# TIVA_1.net
KiCad netlist of a schematic drawn in Altium Designer
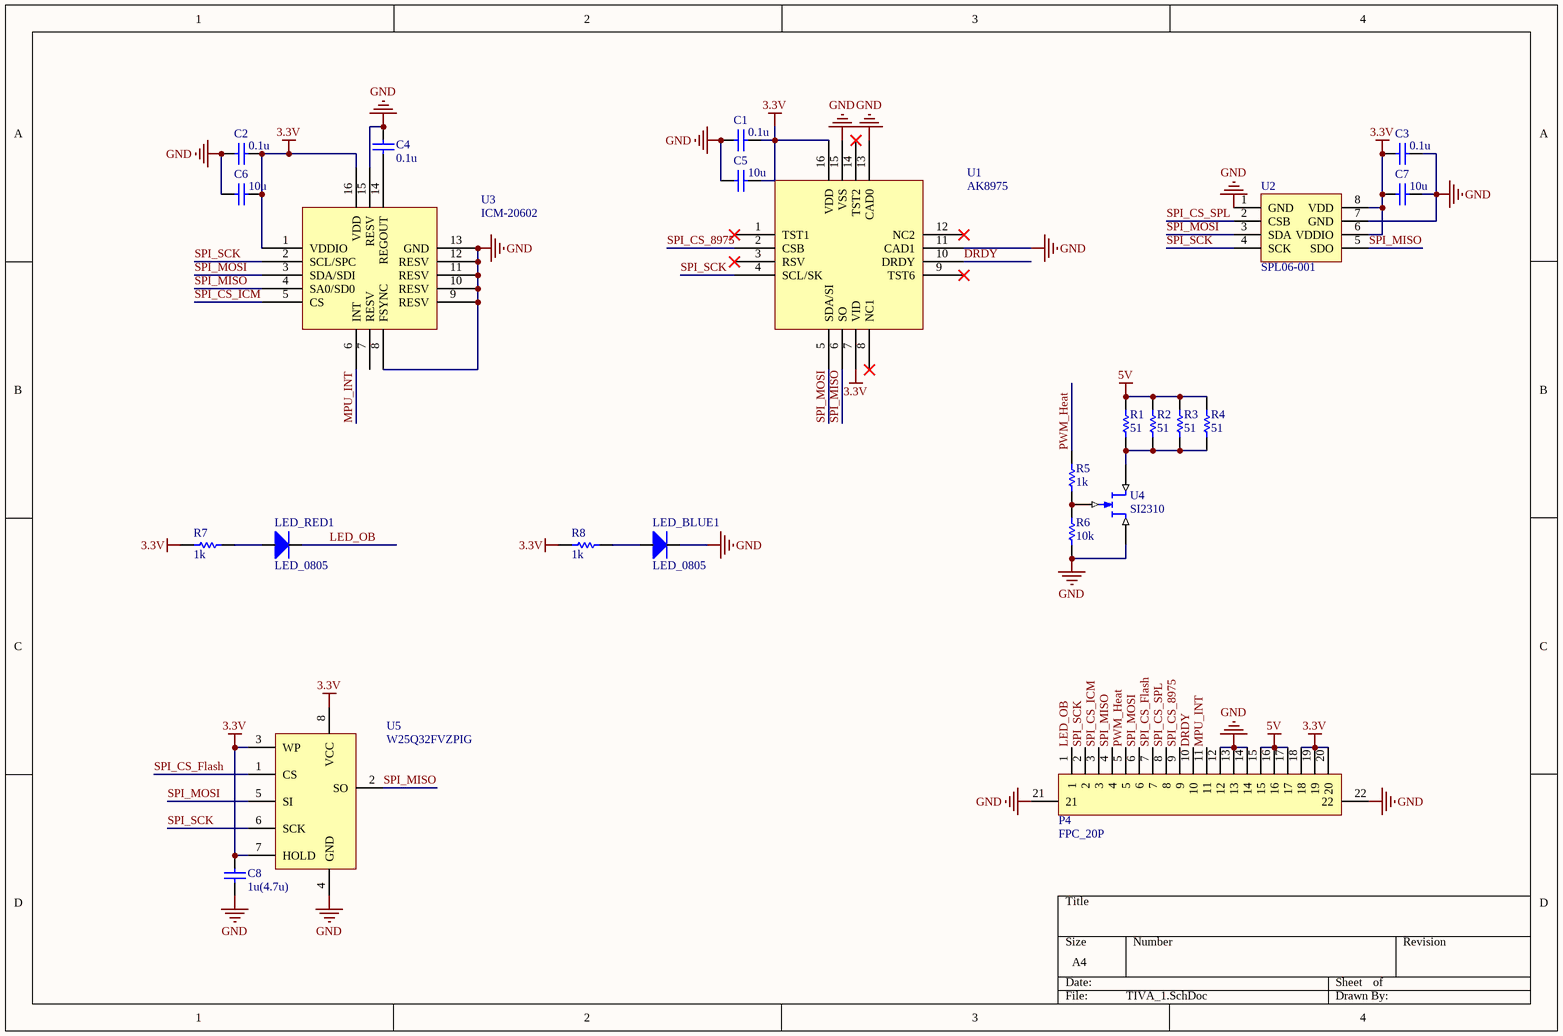
[diagram p0: TIVA_1.SchDoc]

(export (version "E")
  (design (tool "Eeschema 10.0.6"))
  (components
    (comp (ref "C1") (value "0.1u") (footprint "C_0805") (libsource (lib "TIVALib") (part "C_0805")))
    (comp (ref "C2") (value "0.1u") (footprint "C_0805") (libsource (lib "TIVALib") (part "C_0805")))
    (comp (ref "C3") (value "0.1u") (footprint "C_0805") (libsource (lib "TIVALib") (part "C_0805")))
    (comp (ref "C4") (value "0.1u") (footprint "C_0805") (libsource (lib "TIVALib") (part "C_0805")))
    (comp (ref "C5") (value "10u") (footprint "C_0805") (libsource (lib "TIVALib") (part "C_0805")))
    (comp (ref "C6") (value "10u") (footprint "C_0805") (libsource (lib "TIVALib") (part "C_0805")))
    (comp (ref "C7") (value "10u") (footprint "C_0805") (libsource (lib "TIVALib") (part "C_0805")))
    (comp (ref "C8") (value "1u(4.7u)") (footprint "C_0805") (libsource (lib "TIVALib") (part "C_0805")))
    (comp (ref "LED_BLUE1")
      (value "LED_0805")
      (footprint "LED0805")
      (libsource (lib "TIVALib") (part "LED_0805"))
    )
    (comp (ref "LED_RED1")
      (value "LED_0805")
      (footprint "LED0805")
      (libsource (lib "TIVALib") (part "LED_0805"))
    )
    (comp (ref "P4") (value "FPC_20P") (footprint "FPC1.0_20P") (libsource (lib "TIVALib") (part "FPC_20P")))
    (comp (ref "R1") (value "51") (footprint "R_0805") (libsource (lib "TIVALib") (part "R_0805")))
    (comp (ref "R2") (value "51") (footprint "R_0805") (libsource (lib "TIVALib") (part "R_0805")))
    (comp (ref "R3") (value "51") (footprint "R_0805") (libsource (lib "TIVALib") (part "R_0805")))
    (comp (ref "R4") (value "51") (footprint "R_0805") (libsource (lib "TIVALib") (part "R_0805")))
    (comp (ref "R5") (value "1k") (footprint "R_0805") (libsource (lib "TIVALib") (part "R_0805")))
    (comp (ref "R6") (value "10k") (footprint "R_0805") (libsource (lib "TIVALib") (part "R_0805")))
    (comp (ref "R7") (value "1k") (footprint "R_0805") (libsource (lib "TIVALib") (part "R_0805")))
    (comp (ref "R8") (value "1k") (footprint "R_0805") (libsource (lib "TIVALib") (part "R_0805")))
    (comp (ref "U1") (value "AK8975") (footprint "QFN16(4*4)") (libsource (lib "TIVALib") (part "AK8975")))
    (comp (ref "U2")
      (value "SPL06-001")
      (footprint "QFN8(2*4F)")
      (libsource (lib "TIVALib") (part "SPL06-001"))
    )
    (comp (ref "U3")
      (value "ICM-20602")
      (footprint "QFN16(3+5)")
      (libsource (lib "TIVALib") (part "ICM-20602"))
    )
    (comp (ref "U4") (value "SI2310") (footprint "SOT_23") (libsource (lib "TIVALib") (part "SI2310_2")))
    (comp (ref "U5")
      (value "W25Q32FVZPIG")
      (footprint "WSON(6*5mm)")
      (libsource (lib "TIVALib") (part "W25Q32FVZPIG"))
    )
  )
  (nets
    (net (code "1") (name "/DRDY") (class "Default")
      (node (ref "P4") (pin "10") (pinfunction "10_10") (pintype "passive"))
      (node (ref "U1") (pin "10") (pinfunction "DRDY_10") (pintype "passive"))
    )
    (net (code "2") (name "/LED_OB") (class "Default")
      (node (ref "LED_RED1") (pin "2") (pintype "passive"))
      (node (ref "P4") (pin "1") (pinfunction "1_1") (pintype "passive"))
    )
    (net (code "3") (name "/MPU_INT") (class "Default")
      (node (ref "P4") (pin "11") (pinfunction "11_11") (pintype "passive"))
      (node (ref "U3") (pin "6") (pinfunction "INT_6") (pintype "passive"))
    )
    (net (code "4") (name "/PWM_Heat") (class "Default")
      (node (ref "P4") (pin "5") (pinfunction "5_5") (pintype "passive"))
      (node (ref "R5") (pin "2") (pinfunction "2_2") (pintype "passive"))
    )
    (net (code "5") (name "/SPI_CS_8975") (class "Default")
      (node (ref "P4") (pin "9") (pinfunction "9_9") (pintype "passive"))
      (node (ref "U1") (pin "2") (pinfunction "CSB_2") (pintype "passive"))
    )
    (net (code "6") (name "/SPI_CS_Flash") (class "Default")
      (node (ref "P4") (pin "7") (pinfunction "7_7") (pintype "passive"))
      (node (ref "U5") (pin "1") (pinfunction "CS_1") (pintype "passive"))
    )
    (net (code "7") (name "/SPI_CS_ICM") (class "Default")
      (node (ref "P4") (pin "3") (pinfunction "3_3") (pintype "passive"))
      (node (ref "U3") (pin "5") (pinfunction "CS_5") (pintype "passive"))
    )
    (net (code "8") (name "/SPI_CS_SPL") (class "Default")
      (node (ref "P4") (pin "8") (pinfunction "8_8") (pintype "passive"))
      (node (ref "U2") (pin "2") (pinfunction "CSB_2") (pintype "passive"))
    )
    (net (code "9") (name "/SPI_MISO") (class "Default")
      (node (ref "P4") (pin "4") (pinfunction "4_4") (pintype "passive"))
      (node (ref "U1") (pin "6") (pinfunction "SO_6") (pintype "passive"))
      (node (ref "U2") (pin "5") (pinfunction "SDO_5") (pintype "passive"))
      (node (ref "U3") (pin "4") (pinfunction "SA0/SD0_4") (pintype "passive"))
      (node (ref "U5") (pin "2") (pinfunction "SO_2") (pintype "passive"))
    )
    (net (code "10") (name "/SPI_MOSI") (class "Default")
      (node (ref "P4") (pin "6") (pinfunction "6_6") (pintype "passive"))
      (node (ref "U1") (pin "5") (pinfunction "SDA/SI_5") (pintype "passive"))
      (node (ref "U2") (pin "3") (pinfunction "SDA_3") (pintype "passive"))
      (node (ref "U3") (pin "3") (pinfunction "SDA/SDI_3") (pintype "passive"))
      (node (ref "U5") (pin "5") (pinfunction "SI_5") (pintype "passive"))
    )
    (net (code "11") (name "/SPI_SCK") (class "Default")
      (node (ref "P4") (pin "2") (pinfunction "2_2") (pintype "passive"))
      (node (ref "U1") (pin "4") (pinfunction "SCL/SK_4") (pintype "passive"))
      (node (ref "U2") (pin "4") (pinfunction "SCK_4") (pintype "passive"))
      (node (ref "U3") (pin "2") (pinfunction "SCL/SPC_2") (pintype "passive"))
      (node (ref "U5") (pin "6") (pinfunction "SCK_6") (pintype "passive"))
    )
    (net (code "12") (name "3.3V") (class "Default")
      (node (ref "C1") (pin "1") (pinfunction "1_1") (pintype "passive"))
      (node (ref "C2") (pin "1") (pinfunction "1_1") (pintype "passive"))
      (node (ref "C3") (pin "2") (pinfunction "2_2") (pintype "passive"))
      (node (ref "C5") (pin "1") (pinfunction "1_1") (pintype "passive"))
      (node (ref "C6") (pin "1") (pinfunction "1_1") (pintype "passive"))
      (node (ref "C7") (pin "2") (pinfunction "2_2") (pintype "passive"))
      (node (ref "C8") (pin "1") (pinfunction "1_1") (pintype "passive"))
      (node (ref "P4") (pin "18") (pinfunction "18_18") (pintype "passive"))
      (node (ref "P4") (pin "19") (pinfunction "19_19") (pintype "passive"))
      (node (ref "P4") (pin "20") (pinfunction "20_20") (pintype "passive"))
      (node (ref "R7") (pin "1") (pinfunction "1_1") (pintype "passive"))
      (node (ref "R8") (pin "1") (pinfunction "1_1") (pintype "passive"))
      (node (ref "U1") (pin "16") (pinfunction "VDD_16") (pintype "passive"))
      (node (ref "U1") (pin "7") (pinfunction "VID_7") (pintype "passive"))
      (node (ref "U2") (pin "6") (pinfunction "VDDIO_6") (pintype "passive"))
      (node (ref "U2") (pin "8") (pinfunction "VDD_8") (pintype "passive"))
      (node (ref "U3") (pin "1") (pinfunction "VDDIO_1") (pintype "passive"))
      (node (ref "U3") (pin "16") (pinfunction "VDD_16") (pintype "passive"))
      (node (ref "U5") (pin "3") (pinfunction "WP_3") (pintype "passive"))
      (node (ref "U5") (pin "7") (pinfunction "HOLD_7") (pintype "passive"))
      (node (ref "U5") (pin "8") (pinfunction "VCC_8") (pintype "passive"))
    )
    (net (code "13") (name "5V") (class "Default")
      (node (ref "P4") (pin "15") (pinfunction "15_15") (pintype "passive"))
      (node (ref "P4") (pin "16") (pinfunction "16_16") (pintype "passive"))
      (node (ref "P4") (pin "17") (pinfunction "17_17") (pintype "passive"))
      (node (ref "R1") (pin "2") (pinfunction "2_2") (pintype "passive"))
      (node (ref "R2") (pin "2") (pinfunction "2_2") (pintype "passive"))
      (node (ref "R3") (pin "2") (pinfunction "2_2") (pintype "passive"))
      (node (ref "R4") (pin "2") (pinfunction "2_2") (pintype "passive"))
    )
    (net (code "14") (name "GND") (class "Default")
      (node (ref "C1") (pin "2") (pinfunction "2_2") (pintype "passive"))
      (node (ref "C2") (pin "2") (pinfunction "2_2") (pintype "passive"))
      (node (ref "C3") (pin "1") (pinfunction "1_1") (pintype "passive"))
      (node (ref "C4") (pin "2") (pinfunction "2_2") (pintype "passive"))
      (node (ref "C5") (pin "2") (pinfunction "2_2") (pintype "passive"))
      (node (ref "C6") (pin "2") (pinfunction "2_2") (pintype "passive"))
      (node (ref "C7") (pin "1") (pinfunction "1_1") (pintype "passive"))
      (node (ref "C8") (pin "2") (pinfunction "2_2") (pintype "passive"))
      (node (ref "LED_BLUE1") (pin "2") (pintype "passive"))
      (node (ref "P4") (pin "12") (pinfunction "12_12") (pintype "passive"))
      (node (ref "P4") (pin "13") (pinfunction "13_13") (pintype "passive"))
      (node (ref "P4") (pin "14") (pinfunction "14_14") (pintype "passive"))
      (node (ref "P4") (pin "21") (pinfunction "21_21") (pintype "passive"))
      (node (ref "P4") (pin "22") (pinfunction "22_22") (pintype "passive"))
      (node (ref "R6") (pin "1") (pinfunction "1_1") (pintype "passive"))
      (node (ref "U1") (pin "11") (pinfunction "CAD1_11") (pintype "passive"))
      (node (ref "U1") (pin "13") (pinfunction "CAD0_13") (pintype "passive"))
      (node (ref "U1") (pin "15") (pinfunction "VSS_15") (pintype "passive"))
      (node (ref "U2") (pin "1") (pinfunction "GND_1") (pintype "passive"))
      (node (ref "U2") (pin "7") (pinfunction "GND_7") (pintype "passive"))
      (node (ref "U3") (pin "10") (pinfunction "RESV_10") (pintype "passive"))
      (node (ref "U3") (pin "11") (pinfunction "RESV_11") (pintype "passive"))
      (node (ref "U3") (pin "12") (pinfunction "RESV_12") (pintype "passive"))
      (node (ref "U3") (pin "13") (pinfunction "GND_13") (pintype "passive"))
      (node (ref "U3") (pin "15") (pinfunction "RESV_15") (pintype "passive"))
      (node (ref "U3") (pin "8") (pinfunction "FSYNC_8") (pintype "passive"))
      (node (ref "U3") (pin "9") (pinfunction "RESV_9") (pintype "passive"))
      (node (ref "U4") (pin "2") (pinfunction "S_2") (pintype "input"))
      (node (ref "U5") (pin "4") (pinfunction "GND_4") (pintype "passive"))
    )
    (net (code "15") (name "Net-(LED_BLUE1-Pad1)") (class "Default")
      (node (ref "LED_BLUE1") (pin "1") (pintype "passive"))
      (node (ref "R8") (pin "2") (pinfunction "2_2") (pintype "passive"))
    )
    (net (code "16") (name "Net-(LED_RED1-Pad1)") (class "Default")
      (node (ref "LED_RED1") (pin "1") (pintype "passive"))
      (node (ref "R7") (pin "2") (pinfunction "2_2") (pintype "passive"))
    )
    (net (code "17") (name "Net-(U3-REGOUT)") (class "Default")
      (node (ref "C4") (pin "1") (pinfunction "1_1") (pintype "passive"))
      (node (ref "U3") (pin "14") (pinfunction "REGOUT_14") (pintype "passive"))
    )
    (net (code "18") (name "Net-(U4-D)") (class "Default")
      (node (ref "R1") (pin "1") (pinfunction "1_1") (pintype "passive"))
      (node (ref "R2") (pin "1") (pinfunction "1_1") (pintype "passive"))
      (node (ref "R3") (pin "1") (pinfunction "1_1") (pintype "passive"))
      (node (ref "R4") (pin "1") (pinfunction "1_1") (pintype "passive"))
      (node (ref "U4") (pin "3") (pinfunction "D_3") (pintype "input"))
    )
    (net (code "19") (name "Net-(U4-G)") (class "Default")
      (node (ref "R5") (pin "1") (pinfunction "1_1") (pintype "passive"))
      (node (ref "R6") (pin "2") (pinfunction "2_2") (pintype "passive"))
      (node (ref "U4") (pin "1") (pinfunction "G_1") (pintype "input"))
    )
    (net (code "20") (name "unconnected-(U1-NC1-Pad8)") (class "Default")
      (node (ref "U1") (pin "8") (pinfunction "NC1_8") (pintype "passive+no_connect"))
    )
    (net (code "21") (name "unconnected-(U1-NC2-Pad12)") (class "Default")
      (node (ref "U1") (pin "12") (pinfunction "NC2_12") (pintype "passive+no_connect"))
    )
    (net (code "22") (name "unconnected-(U1-RSV-Pad3)") (class "Default")
      (node (ref "U1") (pin "3") (pinfunction "RSV_3") (pintype "passive+no_connect"))
    )
    (net (code "23") (name "unconnected-(U1-TST1-Pad1)") (class "Default")
      (node (ref "U1") (pin "1") (pinfunction "TST1_1") (pintype "passive+no_connect"))
    )
    (net (code "24") (name "unconnected-(U1-TST2-Pad14)") (class "Default")
      (node (ref "U1") (pin "14") (pinfunction "TST2_14") (pintype "passive+no_connect"))
    )
    (net (code "25") (name "unconnected-(U1-TST6-Pad9)") (class "Default")
      (node (ref "U1") (pin "9") (pinfunction "TST6_9") (pintype "passive+no_connect"))
    )
    (net (code "26") (name "unconnected-(U3-RESV-Pad7)") (class "Default")
      (node (ref "U3") (pin "7") (pinfunction "RESV_7") (pintype "passive"))
    )
  )
)
